# untitled.net
KiCad netlist of a schematic drawn in EAGLE
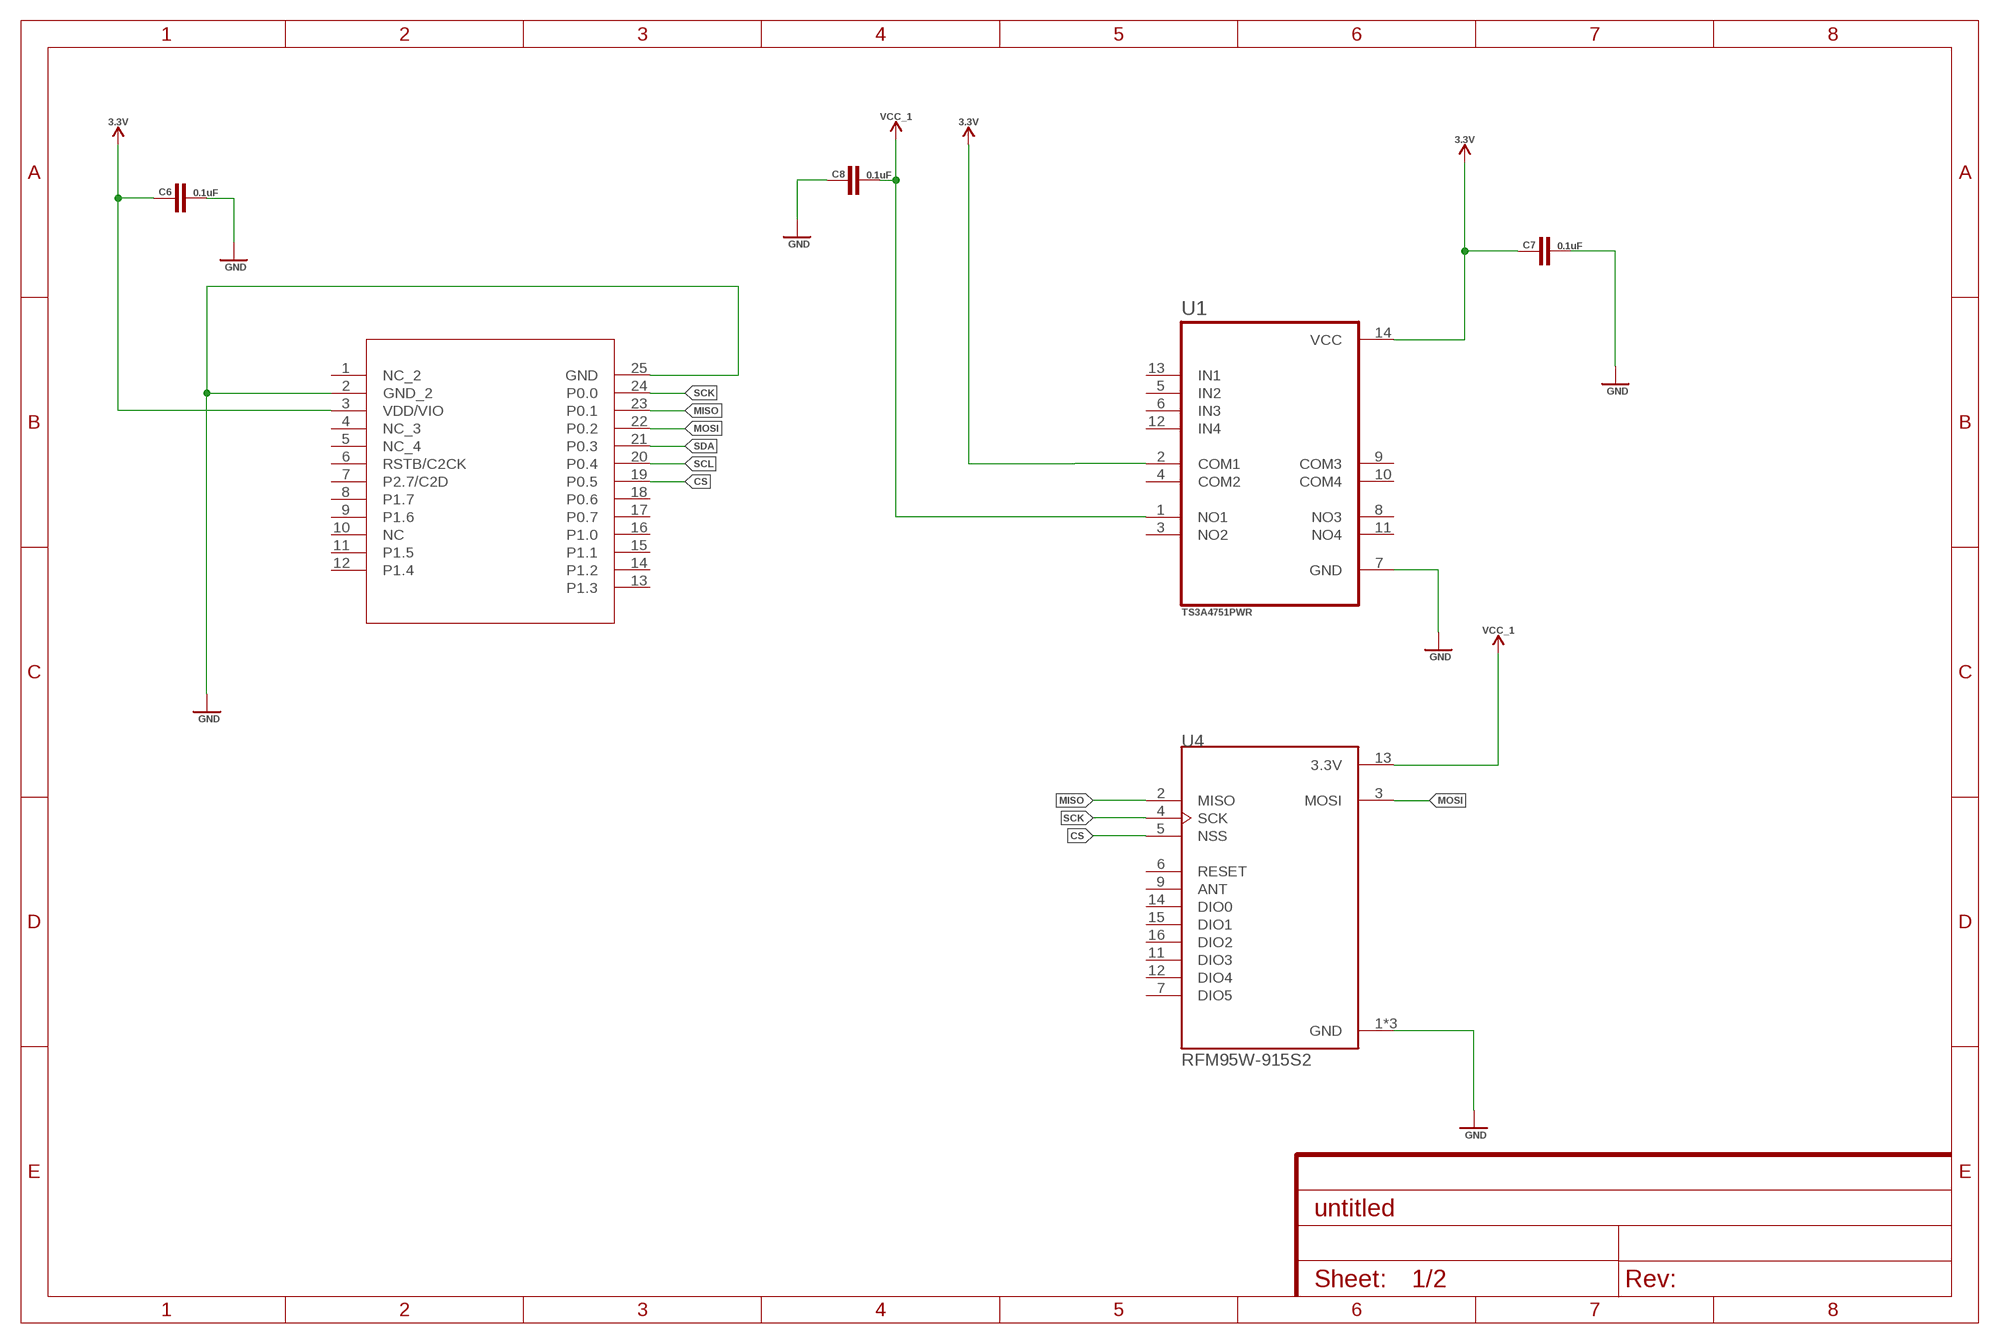
[diagram p0: schematic, sheet 1]
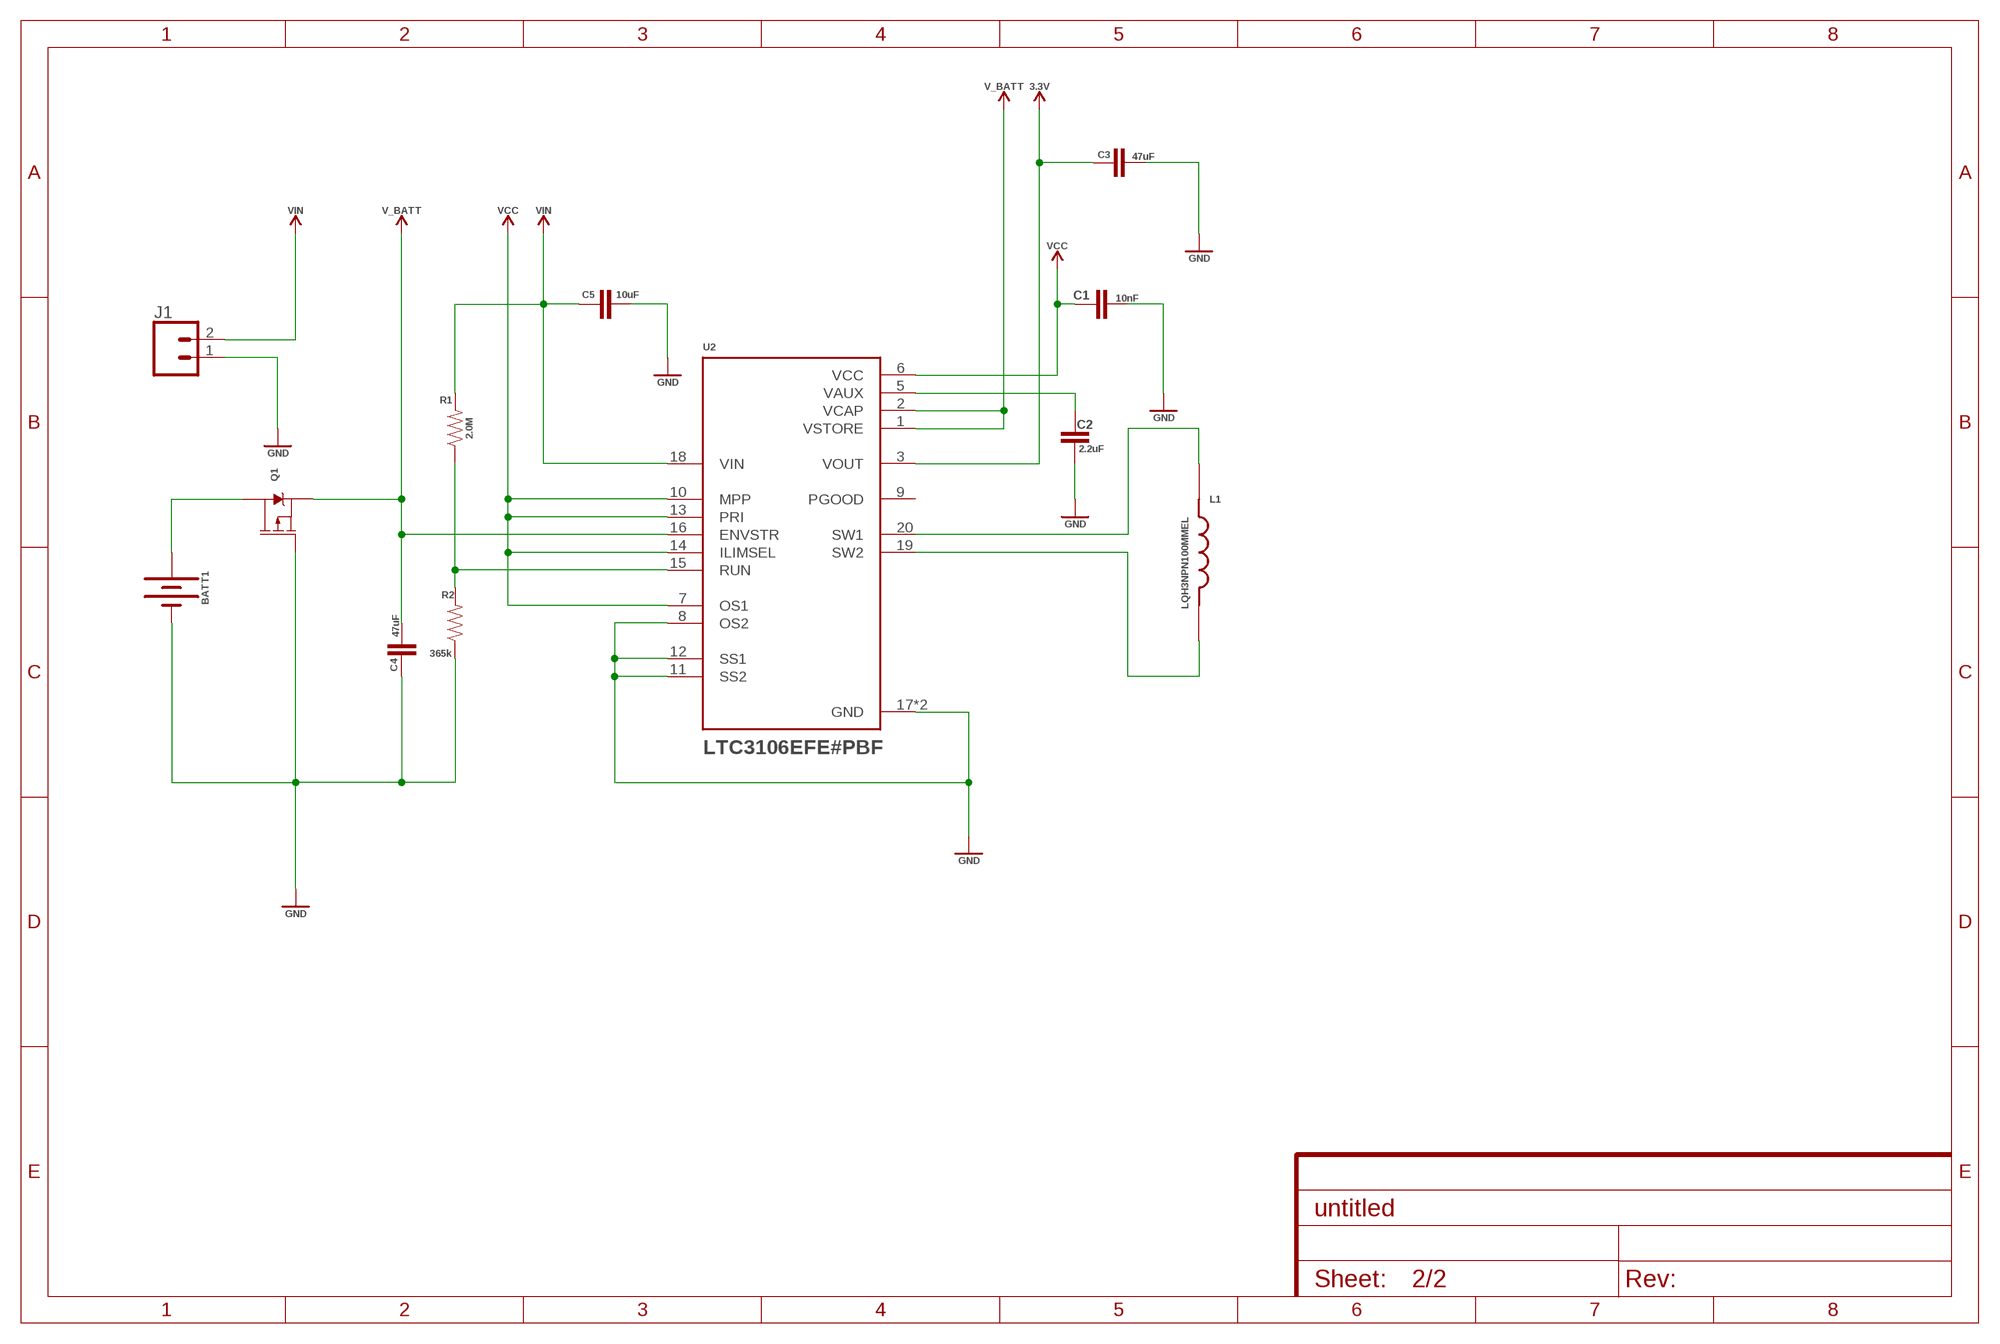
[diagram p1: schematic, sheet 2]

(export (version "E")
  (design (tool "Eeschema 10.0.6"))
  (components
    (comp (ref "C6")
      (value "0.1uF")
      (footprint "eagle-import:0603")
      (libsource (lib "eagle-import") (part "0.1UF-0603-25V-(+80/-20%)"))
    )
    (comp (ref "C7")
      (value "0.1uF")
      (footprint "eagle-import:0603")
      (libsource (lib "eagle-import") (part "0.1UF-0603-25V-(+80/-20%)"))
    )
    (comp (ref "C8")
      (value "0.1uF")
      (footprint "eagle-import:0603")
      (libsource (lib "eagle-import") (part "0.1UF-0603-25V-(+80/-20%)"))
    )
    (comp (ref "U1")
      (value "TS3A4751PWR")
      (footprint "eagle-import:SOP65P640X120-14N")
      (fields (field (name "DIGI-KEY_PART_NUMBER") "296-20700-1-ND") (field (name "MF") "Texas Instruments"))
      (libsource (lib "eagle-import") (part "TS3A4751PWR"))
    )
    (comp (ref "U3")
      (value "EFM8SB10F8G-A-QFN24QFN24_4X4-M")
      (footprint "eagle-import:QFN24_4X4-M")
      (fields
        (field (name "MANUFACTURER_PART_NUMBER") "EFM8SB10F8G-A-QFN24")
        (field (name "COPYRIGHT") "Copyright (C) 2016 Accelerated Designs. All rights reserved")
      )
      (libsource (lib "eagle-import") (part "EFM8SB10F8G-A-QFN24QFN24_4X4-M"))
    )
    (comp (ref "U4")
      (value "RFM95W-915S2")
      (footprint "eagle-import:XCVR_RFM95W-915S2")
      (fields (field (name "MF") "RF Solutions"))
      (libsource (lib "eagle-import") (part "RFM95W-915S2"))
    )
    (comp (ref "BATT1")
      (value "KEYSTONE_54KEYSTONE_2")
      (footprint "eagle-import:KEYSTONE_V2")
      (libsource (lib "eagle-import") (part "KEYSTONE_54KEYSTONE_2"))
    )
    (comp (ref "C1")
      (value "10nF")
      (footprint "eagle-import:0603")
      (libsource (lib "eagle-import") (part "10NF-0603-50V-10%"))
    )
    (comp (ref "C2")
      (value "2.2uF")
      (footprint "eagle-import:0603")
      (libsource (lib "eagle-import") (part "2.2UF-0603-10V-20%"))
    )
    (comp (ref "C3")
      (value "47uF")
      (footprint "eagle-import:0603")
      (libsource (lib "eagle-import") (part "4.7UF0603"))
    )
    (comp (ref "C4")
      (value "47uF")
      (footprint "eagle-import:0603")
      (libsource (lib "eagle-import") (part "4.7UF0603"))
    )
    (comp (ref "C5")
      (value "10uF")
      (footprint "eagle-import:0603")
      (libsource (lib "eagle-import") (part "10UF-0603-6.3V-20%"))
    )
    (comp (ref "J1")
      (value "CONN_023.5MM")
      (footprint "eagle-import:SCREWTERMINAL-3.5MM-2")
      (libsource (lib "eagle-import") (part "CONN_023.5MM"))
    )
    (comp (ref "L1")
      (value "LQH3NPN100MMEL")
      (footprint "eagle-import:IND_LQH3NPN100MMEL")
      (fields (field (name "DIGI-KEY_PART_NUMBER") "490-15945-1-ND") (field (name "MF") "Murata"))
      (libsource (lib "eagle-import") (part "LQH3NPN100MMEL"))
    )
    (comp (ref "Q1")
      (value "2.5A/30V/105mΩ")
      (footprint "eagle-import:SOT23-3")
      (libsource (lib "eagle-import") (part "MOSFET_PCH-DMG2307L"))
    )
    (comp (ref "R1")
      (value "2.0M")
      (footprint "eagle-import:0603")
      (libsource (lib "eagle-import") (part "2MOHMS-0603-1/10W-1%"))
    )
    (comp (ref "R2")
      (value "365k")
      (footprint "eagle-import:0603")
      (libsource (lib "eagle-import") (part "390KOHM-0603-1/10W-1%"))
    )
    (comp (ref "U2")
      (value "LTC3106EFE#PBF")
      (footprint "eagle-import:SOP65P640X120-21N")
      (fields (field (name "MF") "Analog Devices"))
      (libsource (lib "eagle-import") (part "LTC3106EFE#PBF"))
    )
  )
  (nets
    (net (code "1") (name "3.3V") (class "Default")
      (node (ref "C3") (pin "1") (pinfunction "1_1") (pintype "passive"))
      (node (ref "C6") (pin "1") (pinfunction "1_1") (pintype "passive"))
      (node (ref "C7") (pin "1") (pinfunction "1_1") (pintype "passive"))
      (node (ref "U1") (pin "14") (pinfunction "VCC_14") (pintype "power_in"))
      (node (ref "U1") (pin "2") (pinfunction "COM1_2") (pintype "bidirectional"))
      (node (ref "U2") (pin "3") (pinfunction "VOUT_3") (pintype "output"))
      (node (ref "U3") (pin "3") (pinfunction "VDD/VIO_3") (pintype "bidirectional"))
    )
    (net (code "2") (name "CS") (class "Default")
      (node (ref "U3") (pin "19") (pinfunction "P0.5_19") (pintype "bidirectional"))
      (node (ref "U4") (pin "5") (pinfunction "NSS_5") (pintype "input"))
    )
    (net (code "3") (name "GND") (class "Default")
      (node (ref "BATT1") (pin "P$4") (pinfunction "-_P$4") (pintype "power_in"))
      (node (ref "BATT1") (pin "P$5") (pinfunction "-_P$5") (pintype "power_in"))
      (node (ref "BATT1") (pin "P$6") (pinfunction "-_P$6") (pintype "power_in"))
      (node (ref "C1") (pin "2") (pinfunction "2_2") (pintype "passive"))
      (node (ref "C2") (pin "2") (pinfunction "2_2") (pintype "passive"))
      (node (ref "C3") (pin "2") (pinfunction "2_2") (pintype "passive"))
      (node (ref "C4") (pin "1") (pinfunction "1_1") (pintype "passive"))
      (node (ref "C5") (pin "2") (pinfunction "2_2") (pintype "passive"))
      (node (ref "C6") (pin "2") (pinfunction "2_2") (pintype "passive"))
      (node (ref "C7") (pin "2") (pinfunction "2_2") (pintype "passive"))
      (node (ref "C8") (pin "1") (pinfunction "1_1") (pintype "passive"))
      (node (ref "J1") (pin "1") (pinfunction "1_1") (pintype "passive"))
      (node (ref "Q1") (pin "1") (pinfunction "G_1") (pintype "bidirectional"))
      (node (ref "R2") (pin "1") (pinfunction "1_1") (pintype "passive"))
      (node (ref "U1") (pin "7") (pinfunction "GND_7") (pintype "power_in"))
      (node (ref "U2") (pin "11") (pinfunction "SS2_11") (pintype "input"))
      (node (ref "U2") (pin "12") (pinfunction "SS1_12") (pintype "input"))
      (node (ref "U2") (pin "17") (pinfunction "GND_17") (pintype "power_in"))
      (node (ref "U2") (pin "21") (pinfunction "GND_21") (pintype "power_in"))
      (node (ref "U2") (pin "8") (pinfunction "OS2_8") (pintype "input"))
      (node (ref "U3") (pin "2") (pinfunction "GND_2_2") (pintype "power_in"))
      (node (ref "U3") (pin "25") (pinfunction "GND_25") (pintype "power_in"))
      (node (ref "U4") (pin "1") (pinfunction "GND_1") (pintype "power_in"))
      (node (ref "U4") (pin "10") (pinfunction "GND_10") (pintype "power_in"))
      (node (ref "U4") (pin "8") (pinfunction "GND_8") (pintype "power_in"))
    )
    (net (code "4") (name "MISO") (class "Default")
      (node (ref "U3") (pin "23") (pinfunction "P0.1_23") (pintype "bidirectional"))
      (node (ref "U4") (pin "2") (pinfunction "MISO_2") (pintype "input"))
    )
    (net (code "5") (name "MOSI") (class "Default")
      (node (ref "U3") (pin "22") (pinfunction "P0.2_22") (pintype "bidirectional"))
      (node (ref "U4") (pin "3") (pinfunction "MOSI_3") (pintype "output"))
    )
    (net (code "6") (name "Net-(Q1-D)") (class "Default")
      (node (ref "BATT1") (pin "P$1") (pinfunction "+_P$1") (pintype "power_in"))
      (node (ref "BATT1") (pin "P$2") (pinfunction "+_P$2") (pintype "power_in"))
      (node (ref "BATT1") (pin "P$3") (pinfunction "+_P$3") (pintype "power_in"))
      (node (ref "Q1") (pin "3") (pinfunction "D_3") (pintype "bidirectional"))
    )
    (net (code "7") (name "Net-(U2-RUN)") (class "Default")
      (node (ref "R1") (pin "1") (pinfunction "1_1") (pintype "passive"))
      (node (ref "R2") (pin "2") (pinfunction "2_2") (pintype "passive"))
      (node (ref "U2") (pin "15") (pinfunction "RUN_15") (pintype "input"))
    )
    (net (code "8") (name "Net-(U2-SW1)") (class "Default")
      (node (ref "L1") (pin "1") (pinfunction "1_1") (pintype "passive"))
      (node (ref "U2") (pin "20") (pinfunction "SW1_20") (pintype "passive"))
    )
    (net (code "9") (name "Net-(U2-SW2)") (class "Default")
      (node (ref "L1") (pin "2") (pinfunction "2_2") (pintype "passive"))
      (node (ref "U2") (pin "19") (pinfunction "SW2_19") (pintype "passive"))
    )
    (net (code "10") (name "Net-(U2-VAUX)") (class "Default")
      (node (ref "C2") (pin "1") (pinfunction "1_1") (pintype "passive"))
      (node (ref "U2") (pin "5") (pinfunction "VAUX_5") (pintype "power_in"))
    )
    (net (code "11") (name "SCK") (class "Default")
      (node (ref "U3") (pin "24") (pinfunction "P0.0_24") (pintype "bidirectional"))
      (node (ref "U4") (pin "4") (pinfunction "SCK_4") (pintype "input"))
    )
    (net (code "12") (name "SCL") (class "Default")
      (node (ref "U3") (pin "20") (pinfunction "P0.4_20") (pintype "bidirectional"))
    )
    (net (code "13") (name "SDA") (class "Default")
      (node (ref "U3") (pin "21") (pinfunction "P0.3_21") (pintype "bidirectional"))
    )
    (net (code "14") (name "VCC") (class "Default")
      (node (ref "C1") (pin "1") (pinfunction "1_1") (pintype "passive"))
      (node (ref "U2") (pin "10") (pinfunction "MPP_10") (pintype "input"))
      (node (ref "U2") (pin "13") (pinfunction "PRI_13") (pintype "input"))
      (node (ref "U2") (pin "14") (pinfunction "ILIMSEL_14") (pintype "input"))
      (node (ref "U2") (pin "6") (pinfunction "VCC_6") (pintype "power_in"))
      (node (ref "U2") (pin "7") (pinfunction "OS1_7") (pintype "input"))
    )
    (net (code "15") (name "VCC_1") (class "Default")
      (node (ref "C8") (pin "2") (pinfunction "2_2") (pintype "passive"))
      (node (ref "U1") (pin "1") (pinfunction "NO1_1") (pintype "bidirectional"))
      (node (ref "U4") (pin "13") (pinfunction "3.3V_13") (pintype "power_in"))
    )
    (net (code "16") (name "VIN") (class "Default")
      (node (ref "C5") (pin "1") (pinfunction "1_1") (pintype "passive"))
      (node (ref "J1") (pin "2") (pinfunction "2_2") (pintype "passive"))
      (node (ref "R1") (pin "2") (pinfunction "2_2") (pintype "passive"))
      (node (ref "U2") (pin "18") (pinfunction "VIN_18") (pintype "input"))
    )
    (net (code "17") (name "V_BATT") (class "Default")
      (node (ref "C4") (pin "2") (pinfunction "2_2") (pintype "passive"))
      (node (ref "Q1") (pin "2") (pinfunction "S_2") (pintype "bidirectional"))
      (node (ref "U2") (pin "1") (pinfunction "VSTORE_1") (pintype "power_in"))
      (node (ref "U2") (pin "16") (pinfunction "ENVSTR_16") (pintype "input"))
      (node (ref "U2") (pin "2") (pinfunction "VCAP_2") (pintype "power_in"))
    )
    (net (code "18") (name "unconnected-(U1-COM2-Pad4)") (class "Default")
      (node (ref "U1") (pin "4") (pinfunction "COM2_4") (pintype "bidirectional"))
    )
    (net (code "19") (name "unconnected-(U1-COM3-Pad9)") (class "Default")
      (node (ref "U1") (pin "9") (pinfunction "COM3_9") (pintype "bidirectional"))
    )
    (net (code "20") (name "unconnected-(U1-COM4-Pad10)") (class "Default")
      (node (ref "U1") (pin "10") (pinfunction "COM4_10") (pintype "bidirectional"))
    )
    (net (code "21") (name "unconnected-(U1-IN1-Pad13)") (class "Default")
      (node (ref "U1") (pin "13") (pinfunction "IN1_13") (pintype "input"))
    )
    (net (code "22") (name "unconnected-(U1-IN2-Pad5)") (class "Default")
      (node (ref "U1") (pin "5") (pinfunction "IN2_5") (pintype "input"))
    )
    (net (code "23") (name "unconnected-(U1-IN3-Pad6)") (class "Default")
      (node (ref "U1") (pin "6") (pinfunction "IN3_6") (pintype "input"))
    )
    (net (code "24") (name "unconnected-(U1-IN4-Pad12)") (class "Default")
      (node (ref "U1") (pin "12") (pinfunction "IN4_12") (pintype "input"))
    )
    (net (code "25") (name "unconnected-(U1-NO2-Pad3)") (class "Default")
      (node (ref "U1") (pin "3") (pinfunction "NO2_3") (pintype "bidirectional"))
    )
    (net (code "26") (name "unconnected-(U1-NO3-Pad8)") (class "Default")
      (node (ref "U1") (pin "8") (pinfunction "NO3_8") (pintype "bidirectional"))
    )
    (net (code "27") (name "unconnected-(U1-NO4-Pad11)") (class "Default")
      (node (ref "U1") (pin "11") (pinfunction "NO4_11") (pintype "bidirectional"))
    )
    (net (code "28") (name "unconnected-(U2-PGOOD-Pad9)") (class "Default")
      (node (ref "U2") (pin "9") (pinfunction "PGOOD_9") (pintype "output"))
    )
    (net (code "29") (name "unconnected-(U3-NC-Pad10)") (class "Default")
      (node (ref "U3") (pin "10") (pinfunction "NC_10") (pintype "no_connect"))
    )
    (net (code "30") (name "unconnected-(U3-NC_2-Pad1)") (class "Default")
      (node (ref "U3") (pin "1") (pinfunction "NC_2_1") (pintype "no_connect"))
    )
    (net (code "31") (name "unconnected-(U3-NC_3-Pad4)") (class "Default")
      (node (ref "U3") (pin "4") (pinfunction "NC_3_4") (pintype "no_connect"))
    )
    (net (code "32") (name "unconnected-(U3-NC_4-Pad5)") (class "Default")
      (node (ref "U3") (pin "5") (pinfunction "NC_4_5") (pintype "no_connect"))
    )
    (net (code "33") (name "unconnected-(U3-P0.6-Pad18)") (class "Default")
      (node (ref "U3") (pin "18") (pinfunction "P0.6_18") (pintype "bidirectional"))
    )
    (net (code "34") (name "unconnected-(U3-P0.7-Pad17)") (class "Default")
      (node (ref "U3") (pin "17") (pinfunction "P0.7_17") (pintype "bidirectional"))
    )
    (net (code "35") (name "unconnected-(U3-P1.0-Pad16)") (class "Default")
      (node (ref "U3") (pin "16") (pinfunction "P1.0_16") (pintype "bidirectional"))
    )
    (net (code "36") (name "unconnected-(U3-P1.1-Pad15)") (class "Default")
      (node (ref "U3") (pin "15") (pinfunction "P1.1_15") (pintype "bidirectional"))
    )
    (net (code "37") (name "unconnected-(U3-P1.2-Pad14)") (class "Default")
      (node (ref "U3") (pin "14") (pinfunction "P1.2_14") (pintype "bidirectional"))
    )
    (net (code "38") (name "unconnected-(U3-P1.3-Pad13)") (class "Default")
      (node (ref "U3") (pin "13") (pinfunction "P1.3_13") (pintype "bidirectional"))
    )
    (net (code "39") (name "unconnected-(U3-P1.4-Pad12)") (class "Default")
      (node (ref "U3") (pin "12") (pinfunction "P1.4_12") (pintype "bidirectional"))
    )
    (net (code "40") (name "unconnected-(U3-P1.5-Pad11)") (class "Default")
      (node (ref "U3") (pin "11") (pinfunction "P1.5_11") (pintype "bidirectional"))
    )
    (net (code "41") (name "unconnected-(U3-P1.6-Pad9)") (class "Default")
      (node (ref "U3") (pin "9") (pinfunction "P1.6_9") (pintype "bidirectional"))
    )
    (net (code "42") (name "unconnected-(U3-P1.7-Pad8)") (class "Default")
      (node (ref "U3") (pin "8") (pinfunction "P1.7_8") (pintype "bidirectional"))
    )
    (net (code "43") (name "unconnected-(U3-P2.7{slash}C2D-Pad7)") (class "Default")
      (node (ref "U3") (pin "7") (pinfunction "P2.7/C2D_7") (pintype "bidirectional"))
    )
    (net (code "44") (name "unconnected-(U3-RSTB{slash}C2CK-Pad6)") (class "Default")
      (node (ref "U3") (pin "6") (pinfunction "RSTB/C2CK_6") (pintype "bidirectional"))
    )
    (net (code "45") (name "unconnected-(U4-ANT-Pad9)") (class "Default")
      (node (ref "U4") (pin "9") (pinfunction "ANT_9") (pintype "bidirectional"))
    )
    (net (code "46") (name "unconnected-(U4-DIO0-Pad14)") (class "Default")
      (node (ref "U4") (pin "14") (pinfunction "DIO0_14") (pintype "bidirectional"))
    )
    (net (code "47") (name "unconnected-(U4-DIO1-Pad15)") (class "Default")
      (node (ref "U4") (pin "15") (pinfunction "DIO1_15") (pintype "bidirectional"))
    )
    (net (code "48") (name "unconnected-(U4-DIO2-Pad16)") (class "Default")
      (node (ref "U4") (pin "16") (pinfunction "DIO2_16") (pintype "bidirectional"))
    )
    (net (code "49") (name "unconnected-(U4-DIO3-Pad11)") (class "Default")
      (node (ref "U4") (pin "11") (pinfunction "DIO3_11") (pintype "bidirectional"))
    )
    (net (code "50") (name "unconnected-(U4-DIO4-Pad12)") (class "Default")
      (node (ref "U4") (pin "12") (pinfunction "DIO4_12") (pintype "bidirectional"))
    )
    (net (code "51") (name "unconnected-(U4-DIO5-Pad7)") (class "Default")
      (node (ref "U4") (pin "7") (pinfunction "DIO5_7") (pintype "bidirectional"))
    )
    (net (code "52") (name "unconnected-(U4-RESET-Pad6)") (class "Default")
      (node (ref "U4") (pin "6") (pinfunction "RESET_6") (pintype "bidirectional"))
    )
  )
)
